# Iot_board_schematic.net
KiCad netlist of a schematic drawn in Altium Designer
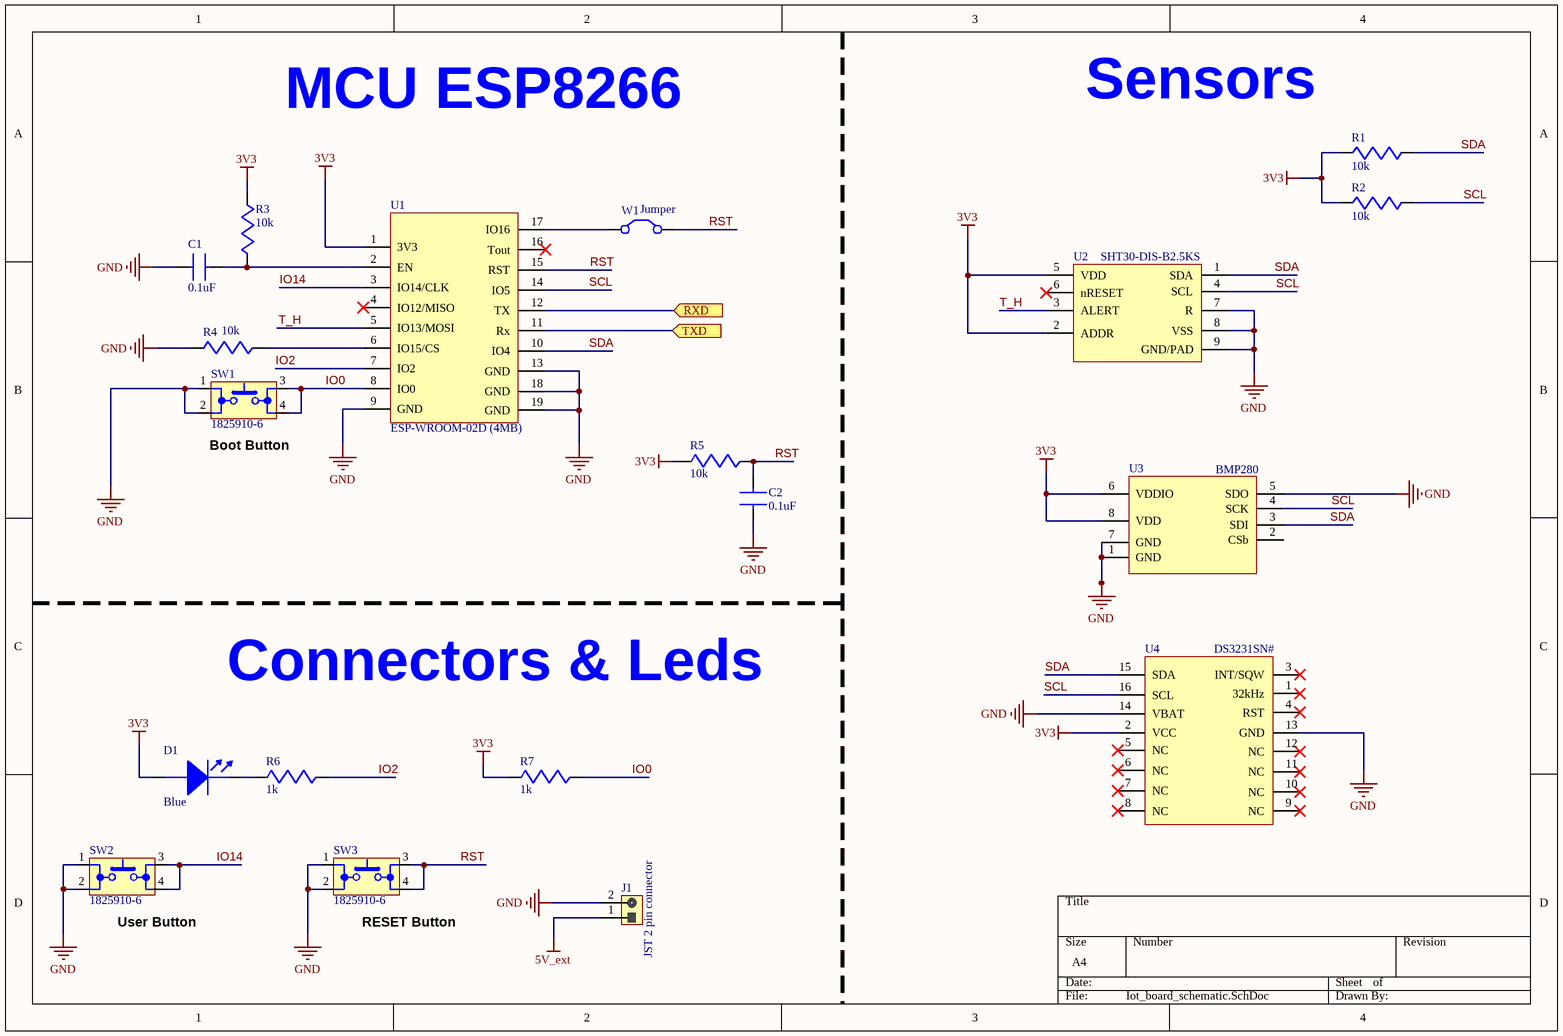
[diagram p0: Iot_board_schematic.SchDoc]

(export (version "E")
  (design (tool "Eeschema 10.0.6"))
  (components
    (comp (ref "C1")
      (value "0.1uF")
      (footprint "C0603")
      (fields
        (field (name "MANUFACTURER") "KEMET")
        (field (name "MANUFACTURER PART NUMBER") "C0603C104K5RACTU")
        (field (name "TOLERANCE") "10%")
      )
      (libsource (lib "Iot_board_schlib") (part "C0603C104K5RACTU"))
    )
    (comp (ref "C2")
      (value "0.1uF")
      (footprint "C0603")
      (fields
        (field (name "MANUFACTURER") "KEMET")
        (field (name "MANUFACTURER PART NUMBER") "C0603C104K5RACTU")
        (field (name "TOLERANCE") "10%")
      )
      (libsource (lib "Iot_board_schlib") (part "C0603C104K5RACTU"))
    )
    (comp (ref "D1")
      (value "Blue")
      (footprint "LED_0603")
      (description "LED BLUE CLEAR 0603 SMD")
      (fields
        (field (name "MANUFACTURER") "Vishay Lite-On")
        (field (name "MANUFACTURER PART NUMBER") "LTST-C191TBKT")
      )
      (libsource (lib "Iot_board_schlib") (part "LTST-C191TBKT"))
    )
    (comp (ref "J1")
      (value "JST 2 pin connector")
      (footprint "JST_2PINS")
      (description "Conn Shrouded Header (4 Sides) HDR 2 POS 2mm Solder RA Thru-Hole Box")
      (fields
        (field (name "MANUFACTURER") "JST")
        (field (name "MANUFACTURER PART NUMBER") "S2B-PH-K-S(LF)(SN)")
      )
      (libsource (lib "Iot_board_schlib") (part "S2B-PH-K-S(LF)(SN)"))
    )
    (comp (ref "R1")
      (value "10k")
      (footprint "R0603")
      (fields
        (field (name "MANUFACTURER") "Vishay")
        (field (name "MANUFACTURER PART NUMBER") "CRCW060310K0FKEA")
        (field (name "TOLERANCE") "1%")
      )
      (libsource (lib "Iot_board_schlib") (part "CRCW060310K0FKEA"))
    )
    (comp (ref "R2")
      (value "10k")
      (footprint "R0603")
      (fields
        (field (name "MANUFACTURER") "Vishay")
        (field (name "MANUFACTURER PART NUMBER") "CRCW060310K0FKEA")
        (field (name "TOLERANCE") "1%")
      )
      (libsource (lib "Iot_board_schlib") (part "CRCW060310K0FKEA"))
    )
    (comp (ref "R3")
      (value "10k")
      (footprint "R0603")
      (fields
        (field (name "MANUFACTURER") "Vishay")
        (field (name "MANUFACTURER PART NUMBER") "CRCW060310K0FKEA")
        (field (name "TOLERANCE") "1%")
      )
      (libsource (lib "Iot_board_schlib") (part "CRCW060310K0FKEA"))
    )
    (comp (ref "R4")
      (value "10k")
      (footprint "R0603")
      (fields
        (field (name "MANUFACTURER") "Vishay")
        (field (name "MANUFACTURER PART NUMBER") "CRCW060310K0FKEA")
        (field (name "TOLERANCE") "1%")
      )
      (libsource (lib "Iot_board_schlib") (part "CRCW060310K0FKEA"))
    )
    (comp (ref "R5")
      (value "10k")
      (footprint "R0603")
      (fields
        (field (name "MANUFACTURER") "Vishay")
        (field (name "MANUFACTURER PART NUMBER") "CRCW060310K0FKEA")
        (field (name "TOLERANCE") "1%")
      )
      (libsource (lib "Iot_board_schlib") (part "CRCW060310K0FKEA"))
    )
    (comp (ref "R6")
      (value "1k")
      (footprint "R0603")
      (fields
        (field (name "MANUFACTURER") "Vishay Dale")
        (field (name "MANUFACTURER PART NUMBER") "CRCW06031K00FKEA")
        (field (name "TOLERANCE") "1%")
      )
      (libsource (lib "Iot_board_schlib") (part "CRCW06031K00FKEA"))
    )
    (comp (ref "R7")
      (value "1k")
      (footprint "R0603")
      (fields
        (field (name "MANUFACTURER") "Vishay Dale")
        (field (name "MANUFACTURER PART NUMBER") "CRCW06031K00FKEA")
        (field (name "TOLERANCE") "1%")
      )
      (libsource (lib "Iot_board_schlib") (part "CRCW06031K00FKEA"))
    )
    (comp (ref "SW1")
      (value "1825910-6")
      (footprint "1825910-6")
      (description "SWITCH TACTILE SPST-NO 0.05A 24V")
      (fields (field (name "MANUFACTURER") "TE Connectivity Alcoswitch"))
      (libsource (lib "Iot_board_schlib") (part "1825910-6"))
    )
    (comp (ref "SW2")
      (value "1825910-6")
      (footprint "1825910-6")
      (description "SWITCH TACTILE SPST-NO 0.05A 24V")
      (fields (field (name "MANUFACTURER") "TE Connectivity Alcoswitch"))
      (libsource (lib "Iot_board_schlib") (part "1825910-6"))
    )
    (comp (ref "SW3")
      (value "1825910-6")
      (footprint "1825910-6")
      (description "SWITCH TACTILE SPST-NO 0.05A 24V")
      (fields (field (name "MANUFACTURER") "TE Connectivity Alcoswitch"))
      (libsource (lib "Iot_board_schlib") (part "1825910-6"))
    )
    (comp (ref "U1")
      (value "ESP-WROOM-02D (4MB)")
      (footprint "MODULE_ESP-WROOM-02")
      (fields (field (name "MANUFACTURER") "Espressif Systems"))
      (libsource (lib "Iot_board_schlib") (part "ESP-WROOM-02D (4MB)"))
    )
    (comp (ref "U2")
      (value "SHT30-DIS-B2.5KS")
      (footprint "QFN8")
      (description "Humidity/Temperature Sensor Digital Serial (I2C) 8-Pin DFN EP T/R")
      (fields (field (name "MANUFACTURER") "Sensirion"))
      (libsource (lib "Iot_board_schlib") (part "SHT30-DIS-B2.5KS"))
    )
    (comp (ref "U3")
      (value "BMP280")
      (footprint "LGA8")
      (description "BMP280 Absolute Barometric Pressure Sensor for Battery Powered Devices 2 x 2.5mm")
      (fields (field (name "MANUFACTURER") "Bosch"))
      (libsource (lib "Iot_board_schlib") (part "BMP280"))
    )
    (comp (ref "U4")
      (value "DS3231SN#")
      (footprint "SOP16")
      (description "RTC, TCXO, CRYSTAL, 3.3V, 16SOIC")
      (fields (field (name "MANUFACTURER") "Maxim"))
      (libsource (lib "Iot_board_schlib") (part "DS3231SN#"))
    )
    (comp (ref "W1")
      (value "Jumper")
      (footprint "RAD-0.2")
      (description "Jumper Wire")
      (fields (field (name "PUBLISHER") "Altium Limited"))
      (libsource (lib "Miscellaneous Devices") (part "Jumper"))
    )
  )
  (nets
    (net (code "1") (name "/IO0") (class "Default")
      (node (ref "R7") (pin "1") (pinfunction "1_1") (pintype "passive"))
      (node (ref "SW1") (pin "3") (pinfunction "3_3") (pintype "passive"))
      (node (ref "SW1") (pin "4") (pinfunction "4_4") (pintype "passive"))
      (node (ref "U1") (pin "8") (pinfunction "IO0_8") (pintype "passive"))
    )
    (net (code "2") (name "/IO2") (class "Default")
      (node (ref "R6") (pin "1") (pinfunction "1_1") (pintype "passive"))
      (node (ref "U1") (pin "7") (pinfunction "IO2_7") (pintype "passive"))
    )
    (net (code "3") (name "/IO14") (class "Default")
      (node (ref "SW2") (pin "3") (pinfunction "3_3") (pintype "passive"))
      (node (ref "SW2") (pin "4") (pinfunction "4_4") (pintype "passive"))
      (node (ref "U1") (pin "3") (pinfunction "IO14/CLK_3") (pintype "passive"))
    )
    (net (code "4") (name "/RST") (class "Default")
      (node (ref "C2") (pin "2") (pinfunction "2_2") (pintype "passive"))
      (node (ref "R5") (pin "1") (pinfunction "1_1") (pintype "passive"))
      (node (ref "SW3") (pin "3") (pinfunction "3_3") (pintype "passive"))
      (node (ref "SW3") (pin "4") (pinfunction "4_4") (pintype "passive"))
      (node (ref "U1") (pin "15") (pinfunction "RST_15") (pintype "passive"))
      (node (ref "W1") (pin "2") (pinfunction "C2_2") (pintype "passive"))
    )
    (net (code "5") (name "/RXD") (class "Default")
      (node (ref "U1") (pin "12") (pinfunction "TX_12") (pintype "passive"))
    )
    (net (code "6") (name "/SCL") (class "Default")
      (node (ref "R2") (pin "2") (pinfunction "2_2") (pintype "passive"))
      (node (ref "U1") (pin "14") (pinfunction "IO5_14") (pintype "passive"))
      (node (ref "U2") (pin "4") (pinfunction "SCL_4") (pintype "passive"))
      (node (ref "U3") (pin "4") (pinfunction "SCK_4") (pintype "passive"))
      (node (ref "U4") (pin "16") (pinfunction "SCL_16") (pintype "passive"))
    )
    (net (code "7") (name "/SDA") (class "Default")
      (node (ref "R1") (pin "2") (pinfunction "2_2") (pintype "passive"))
      (node (ref "U1") (pin "10") (pinfunction "IO4_10") (pintype "passive"))
      (node (ref "U2") (pin "1") (pinfunction "SDA_1") (pintype "passive"))
      (node (ref "U3") (pin "3") (pinfunction "SDI_3") (pintype "passive"))
      (node (ref "U4") (pin "15") (pinfunction "SDA_15") (pintype "passive"))
    )
    (net (code "8") (name "/TXD") (class "Default")
      (node (ref "U1") (pin "11") (pinfunction "Rx_11") (pintype "passive"))
    )
    (net (code "9") (name "/T_H") (class "Default")
      (node (ref "U1") (pin "5") (pinfunction "IO13/MOSI_5") (pintype "passive"))
      (node (ref "U2") (pin "3") (pinfunction "ALERT_3") (pintype "passive"))
    )
    (net (code "10") (name "3V3") (class "Default")
      (node (ref "D1") (pin "2") (pinfunction "Anode_2") (pintype "passive"))
      (node (ref "R1") (pin "1") (pinfunction "1_1") (pintype "passive"))
      (node (ref "R2") (pin "1") (pinfunction "1_1") (pintype "passive"))
      (node (ref "R3") (pin "2") (pinfunction "2_2") (pintype "passive"))
      (node (ref "R5") (pin "2") (pinfunction "2_2") (pintype "passive"))
      (node (ref "R7") (pin "2") (pinfunction "2_2") (pintype "passive"))
      (node (ref "U1") (pin "1") (pinfunction "3V3_1") (pintype "passive"))
      (node (ref "U2") (pin "2") (pinfunction "ADDR_2") (pintype "passive"))
      (node (ref "U2") (pin "5") (pinfunction "VDD_5") (pintype "passive"))
      (node (ref "U3") (pin "6") (pinfunction "VDDIO_6") (pintype "passive"))
      (node (ref "U3") (pin "8") (pinfunction "VDD_8") (pintype "passive"))
      (node (ref "U4") (pin "2") (pinfunction "VCC_2") (pintype "passive"))
    )
    (net (code "11") (name "5V_ext") (class "Default")
      (node (ref "J1") (pin "1") (pinfunction "1_1") (pintype "passive"))
    )
    (net (code "12") (name "GND") (class "Default")
      (node (ref "C1") (pin "1") (pinfunction "1_1") (pintype "passive"))
      (node (ref "C2") (pin "1") (pinfunction "1_1") (pintype "passive"))
      (node (ref "J1") (pin "2") (pinfunction "2_2") (pintype "passive"))
      (node (ref "R4") (pin "2") (pinfunction "2_2") (pintype "passive"))
      (node (ref "SW1") (pin "1") (pinfunction "1_1") (pintype "passive"))
      (node (ref "SW1") (pin "2") (pinfunction "2_2") (pintype "passive"))
      (node (ref "SW2") (pin "1") (pinfunction "1_1") (pintype "passive"))
      (node (ref "SW2") (pin "2") (pinfunction "2_2") (pintype "passive"))
      (node (ref "SW3") (pin "1") (pinfunction "1_1") (pintype "passive"))
      (node (ref "SW3") (pin "2") (pinfunction "2_2") (pintype "passive"))
      (node (ref "U1") (pin "13") (pinfunction "GND_13") (pintype "passive"))
      (node (ref "U1") (pin "18") (pinfunction "GND_18") (pintype "passive"))
      (node (ref "U1") (pin "19") (pinfunction "GND_19") (pintype "passive"))
      (node (ref "U1") (pin "9") (pinfunction "GND_9") (pintype "passive"))
      (node (ref "U2") (pin "7") (pinfunction "R_7") (pintype "passive"))
      (node (ref "U2") (pin "8") (pinfunction "VSS_8") (pintype "passive"))
      (node (ref "U2") (pin "9") (pinfunction "GND/PAD_9") (pintype "passive"))
      (node (ref "U3") (pin "1") (pinfunction "GND_1") (pintype "passive"))
      (node (ref "U3") (pin "5") (pinfunction "SDO_5") (pintype "passive"))
      (node (ref "U3") (pin "7") (pinfunction "GND_7") (pintype "passive"))
      (node (ref "U4") (pin "13") (pinfunction "GND_13") (pintype "passive"))
      (node (ref "U4") (pin "14") (pinfunction "VBAT_14") (pintype "passive"))
    )
    (net (code "13") (name "Net-(D1-Cathode)") (class "Default")
      (node (ref "D1") (pin "1") (pinfunction "Cathode_1") (pintype "passive"))
      (node (ref "R6") (pin "2") (pinfunction "2_2") (pintype "passive"))
    )
    (net (code "14") (name "Net-(U1-EN)") (class "Default")
      (node (ref "C1") (pin "2") (pinfunction "2_2") (pintype "passive"))
      (node (ref "R3") (pin "1") (pinfunction "1_1") (pintype "passive"))
      (node (ref "U1") (pin "2") (pinfunction "EN_2") (pintype "passive"))
    )
    (net (code "15") (name "Net-(U1-IO15{slash}CS)") (class "Default")
      (node (ref "R4") (pin "1") (pinfunction "1_1") (pintype "passive"))
      (node (ref "U1") (pin "6") (pinfunction "IO15/CS_6") (pintype "passive"))
    )
    (net (code "16") (name "Net-(U1-IO16)") (class "Default")
      (node (ref "U1") (pin "17") (pinfunction "IO16_17") (pintype "passive"))
      (node (ref "W1") (pin "1") (pinfunction "C1_1") (pintype "passive"))
    )
    (net (code "17") (name "unconnected-(U1-IO12{slash}MISO-Pad4)") (class "Default")
      (node (ref "U1") (pin "4") (pinfunction "IO12/MISO_4") (pintype "passive+no_connect"))
    )
    (net (code "18") (name "unconnected-(U1-Tout-Pad16)") (class "Default")
      (node (ref "U1") (pin "16") (pinfunction "Tout_16") (pintype "passive+no_connect"))
    )
    (net (code "19") (name "unconnected-(U2-nRESET-Pad6)") (class "Default")
      (node (ref "U2") (pin "6") (pinfunction "nRESET_6") (pintype "passive+no_connect"))
    )
    (net (code "20") (name "unconnected-(U3-CSb-Pad2)") (class "Default")
      (node (ref "U3") (pin "2") (pinfunction "CSb_2") (pintype "passive"))
    )
    (net (code "21") (name "unconnected-(U4-32kHz-Pad1)") (class "Default")
      (node (ref "U4") (pin "1") (pinfunction "32kHz_1") (pintype "passive+no_connect"))
    )
    (net (code "22") (name "unconnected-(U4-INT{slash}SQW-Pad3)") (class "Default")
      (node (ref "U4") (pin "3") (pinfunction "INT/SQW_3") (pintype "passive+no_connect"))
    )
    (net (code "23") (name "unconnected-(U4-NC-Pad5)") (class "Default")
      (node (ref "U4") (pin "5") (pinfunction "NC_5") (pintype "passive+no_connect"))
    )
    (net (code "24") (name "unconnected-(U4-NC-Pad6)") (class "Default")
      (node (ref "U4") (pin "6") (pinfunction "NC_6") (pintype "passive+no_connect"))
    )
    (net (code "25") (name "unconnected-(U4-NC-Pad7)") (class "Default")
      (node (ref "U4") (pin "7") (pinfunction "NC_7") (pintype "passive+no_connect"))
    )
    (net (code "26") (name "unconnected-(U4-NC-Pad8)") (class "Default")
      (node (ref "U4") (pin "8") (pinfunction "NC_8") (pintype "passive+no_connect"))
    )
    (net (code "27") (name "unconnected-(U4-NC-Pad9)") (class "Default")
      (node (ref "U4") (pin "9") (pinfunction "NC_9") (pintype "passive+no_connect"))
    )
    (net (code "28") (name "unconnected-(U4-NC-Pad10)") (class "Default")
      (node (ref "U4") (pin "10") (pinfunction "NC_10") (pintype "passive+no_connect"))
    )
    (net (code "29") (name "unconnected-(U4-NC-Pad11)") (class "Default")
      (node (ref "U4") (pin "11") (pinfunction "NC_11") (pintype "passive+no_connect"))
    )
    (net (code "30") (name "unconnected-(U4-NC-Pad12)") (class "Default")
      (node (ref "U4") (pin "12") (pinfunction "NC_12") (pintype "passive+no_connect"))
    )
    (net (code "31") (name "unconnected-(U4-RST-Pad4)") (class "Default")
      (node (ref "U4") (pin "4") (pinfunction "RST_4") (pintype "passive+no_connect"))
    )
  )
)
